# ArduinoMega.net
KiCad netlist of a schematic drawn in Altium Designer
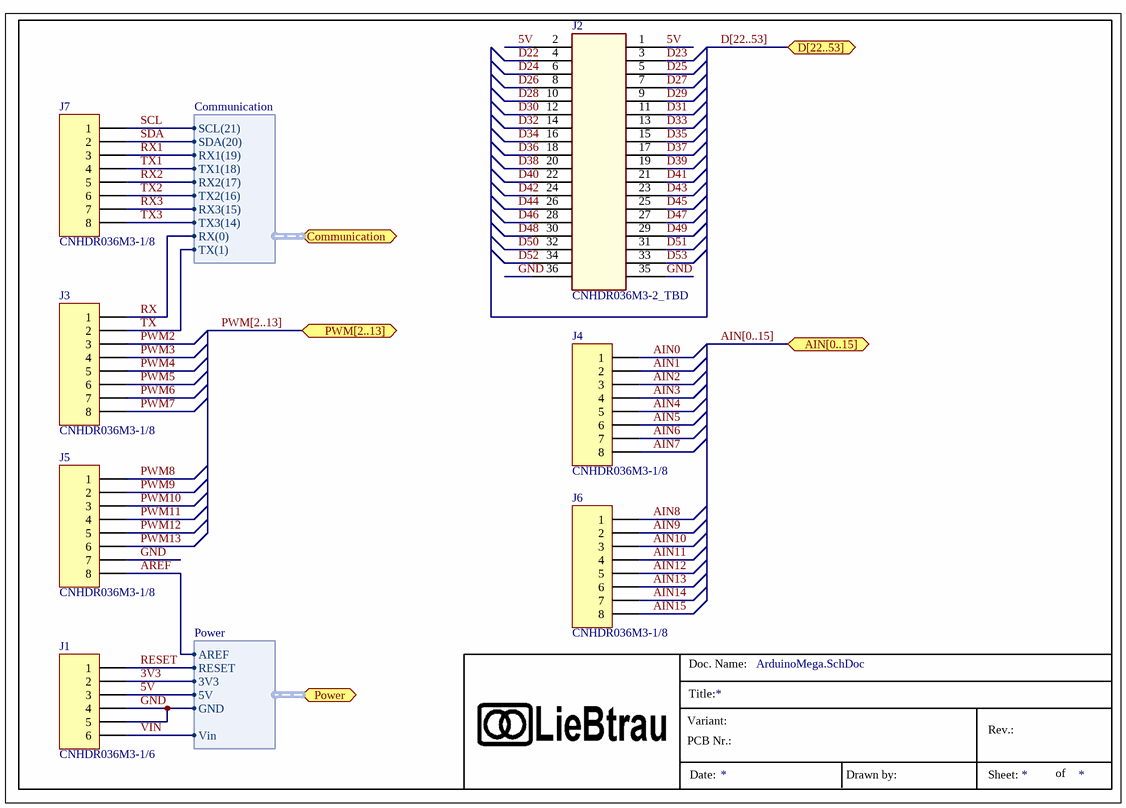
[diagram p0: ArduinoMega.SchDoc]

(export (version "E")
  (design (tool "Eeschema 10.0.6"))
  (components
    (comp (ref "J1")
      (value "CNHDR036M3-1/6")
      (footprint "J_HDR1X6")
      (libsource (lib "Testing") (part "J_6P"))
    )
    (comp (ref "J2")
      (value "CNHDR036M3-2_TBD")
      (footprint "J_HDR2X18")
      (libsource (lib "Testing") (part "J_2X18P"))
    )
    (comp (ref "J3")
      (value "CNHDR036M3-1/8")
      (footprint "J_HDR1X8")
      (libsource (lib "Testing") (part "J_8P"))
    )
    (comp (ref "J4")
      (value "CNHDR036M3-1/8")
      (footprint "J_HDR1X8")
      (libsource (lib "Testing") (part "J_8P"))
    )
    (comp (ref "J5")
      (value "CNHDR036M3-1/8")
      (footprint "J_HDR1X8")
      (libsource (lib "Testing") (part "J_8P"))
    )
    (comp (ref "J6")
      (value "CNHDR036M3-1/8")
      (footprint "J_HDR1X8")
      (libsource (lib "Testing") (part "J_8P"))
    )
    (comp (ref "J7")
      (value "CNHDR036M3-1/8")
      (footprint "J_HDR1X8")
      (libsource (lib "Testing") (part "J_8P"))
    )
  )
  (nets
    (net (code "3") (name "/3V3") (class "Default")
      (node (ref "J1") (pin "2") (pinfunction "2_2") (pintype "passive"))
    )
    (net (code "4") (name "/5V") (class "Default")
      (node (ref "J1") (pin "3") (pinfunction "3_3") (pintype "passive"))
      (node (ref "J2") (pin "1") (pinfunction "1_1") (pintype "passive"))
      (node (ref "J2") (pin "2") (pinfunction "2_2") (pintype "passive"))
    )
    (net (code "5") (name "/AIN0") (class "Default")
      (node (ref "J4") (pin "1") (pinfunction "1_1") (pintype "passive"))
    )
    (net (code "6") (name "/AIN1") (class "Default")
      (node (ref "J4") (pin "2") (pinfunction "2_2") (pintype "passive"))
    )
    (net (code "7") (name "/AIN2") (class "Default")
      (node (ref "J4") (pin "3") (pinfunction "3_3") (pintype "passive"))
    )
    (net (code "8") (name "/AIN3") (class "Default")
      (node (ref "J4") (pin "4") (pinfunction "4_4") (pintype "passive"))
    )
    (net (code "9") (name "/AIN4") (class "Default")
      (node (ref "J4") (pin "5") (pinfunction "5_5") (pintype "passive"))
    )
    (net (code "10") (name "/AIN5") (class "Default")
      (node (ref "J4") (pin "6") (pinfunction "6_6") (pintype "passive"))
    )
    (net (code "11") (name "/AIN6") (class "Default")
      (node (ref "J4") (pin "7") (pinfunction "7_7") (pintype "passive"))
    )
    (net (code "12") (name "/AIN7") (class "Default")
      (node (ref "J4") (pin "8") (pinfunction "8_8") (pintype "passive"))
    )
    (net (code "13") (name "/AIN8") (class "Default")
      (node (ref "J6") (pin "1") (pinfunction "1_1") (pintype "passive"))
    )
    (net (code "14") (name "/AIN9") (class "Default")
      (node (ref "J6") (pin "2") (pinfunction "2_2") (pintype "passive"))
    )
    (net (code "15") (name "/AIN10") (class "Default")
      (node (ref "J6") (pin "3") (pinfunction "3_3") (pintype "passive"))
    )
    (net (code "16") (name "/AIN11") (class "Default")
      (node (ref "J6") (pin "4") (pinfunction "4_4") (pintype "passive"))
    )
    (net (code "17") (name "/AIN12") (class "Default")
      (node (ref "J6") (pin "5") (pinfunction "5_5") (pintype "passive"))
    )
    (net (code "18") (name "/AIN13") (class "Default")
      (node (ref "J6") (pin "6") (pinfunction "6_6") (pintype "passive"))
    )
    (net (code "19") (name "/AIN14") (class "Default")
      (node (ref "J6") (pin "7") (pinfunction "7_7") (pintype "passive"))
    )
    (net (code "20") (name "/AIN15") (class "Default")
      (node (ref "J6") (pin "8") (pinfunction "8_8") (pintype "passive"))
    )
    (net (code "22") (name "/AREF") (class "Default")
      (node (ref "J5") (pin "8") (pinfunction "8_8") (pintype "passive"))
    )
    (net (code "23") (name "/D22") (class "Default")
      (node (ref "J2") (pin "4") (pinfunction "4_4") (pintype "passive"))
    )
    (net (code "24") (name "/D23") (class "Default")
      (node (ref "J2") (pin "3") (pinfunction "3_3") (pintype "passive"))
    )
    (net (code "25") (name "/D24") (class "Default")
      (node (ref "J2") (pin "6") (pinfunction "6_6") (pintype "passive"))
    )
    (net (code "26") (name "/D25") (class "Default")
      (node (ref "J2") (pin "5") (pinfunction "5_5") (pintype "passive"))
    )
    (net (code "27") (name "/D26") (class "Default")
      (node (ref "J2") (pin "8") (pinfunction "8_8") (pintype "passive"))
    )
    (net (code "28") (name "/D27") (class "Default")
      (node (ref "J2") (pin "7") (pinfunction "7_7") (pintype "passive"))
    )
    (net (code "29") (name "/D28") (class "Default")
      (node (ref "J2") (pin "10") (pinfunction "10_10") (pintype "passive"))
    )
    (net (code "30") (name "/D29") (class "Default")
      (node (ref "J2") (pin "9") (pinfunction "9_9") (pintype "passive"))
    )
    (net (code "31") (name "/D30") (class "Default")
      (node (ref "J2") (pin "12") (pinfunction "12_12") (pintype "passive"))
    )
    (net (code "32") (name "/D31") (class "Default")
      (node (ref "J2") (pin "11") (pinfunction "11_11") (pintype "passive"))
    )
    (net (code "33") (name "/D32") (class "Default")
      (node (ref "J2") (pin "14") (pinfunction "14_14") (pintype "passive"))
    )
    (net (code "34") (name "/D33") (class "Default")
      (node (ref "J2") (pin "13") (pinfunction "13_13") (pintype "passive"))
    )
    (net (code "35") (name "/D34") (class "Default")
      (node (ref "J2") (pin "16") (pinfunction "16_16") (pintype "passive"))
    )
    (net (code "36") (name "/D35") (class "Default")
      (node (ref "J2") (pin "15") (pinfunction "15_15") (pintype "passive"))
    )
    (net (code "37") (name "/D36") (class "Default")
      (node (ref "J2") (pin "18") (pinfunction "18_18") (pintype "passive"))
    )
    (net (code "38") (name "/D37") (class "Default")
      (node (ref "J2") (pin "17") (pinfunction "17_17") (pintype "passive"))
    )
    (net (code "39") (name "/D38") (class "Default")
      (node (ref "J2") (pin "20") (pinfunction "20_20") (pintype "passive"))
    )
    (net (code "40") (name "/D39") (class "Default")
      (node (ref "J2") (pin "19") (pinfunction "19_19") (pintype "passive"))
    )
    (net (code "41") (name "/D40") (class "Default")
      (node (ref "J2") (pin "22") (pinfunction "22_22") (pintype "passive"))
    )
    (net (code "42") (name "/D41") (class "Default")
      (node (ref "J2") (pin "21") (pinfunction "21_21") (pintype "passive"))
    )
    (net (code "43") (name "/D42") (class "Default")
      (node (ref "J2") (pin "24") (pinfunction "24_24") (pintype "passive"))
    )
    (net (code "44") (name "/D43") (class "Default")
      (node (ref "J2") (pin "23") (pinfunction "23_23") (pintype "passive"))
    )
    (net (code "45") (name "/D44") (class "Default")
      (node (ref "J2") (pin "26") (pinfunction "26_26") (pintype "passive"))
    )
    (net (code "46") (name "/D45") (class "Default")
      (node (ref "J2") (pin "25") (pinfunction "25_25") (pintype "passive"))
    )
    (net (code "47") (name "/D46") (class "Default")
      (node (ref "J2") (pin "28") (pinfunction "28_28") (pintype "passive"))
    )
    (net (code "48") (name "/D47") (class "Default")
      (node (ref "J2") (pin "27") (pinfunction "27_27") (pintype "passive"))
    )
    (net (code "49") (name "/D48") (class "Default")
      (node (ref "J2") (pin "30") (pinfunction "30_30") (pintype "passive"))
    )
    (net (code "50") (name "/D49") (class "Default")
      (node (ref "J2") (pin "29") (pinfunction "29_29") (pintype "passive"))
    )
    (net (code "51") (name "/D50") (class "Default")
      (node (ref "J2") (pin "32") (pinfunction "32_32") (pintype "passive"))
    )
    (net (code "52") (name "/D51") (class "Default")
      (node (ref "J2") (pin "31") (pinfunction "31_31") (pintype "passive"))
    )
    (net (code "53") (name "/D52") (class "Default")
      (node (ref "J2") (pin "34") (pinfunction "34_34") (pintype "passive"))
    )
    (net (code "54") (name "/D53") (class "Default")
      (node (ref "J2") (pin "33") (pinfunction "33_33") (pintype "passive"))
    )
    (net (code "56") (name "/GND") (class "Default")
      (node (ref "J1") (pin "4") (pinfunction "4_4") (pintype "passive"))
      (node (ref "J1") (pin "5") (pinfunction "5_5") (pintype "passive"))
      (node (ref "J2") (pin "35") (pinfunction "35_35") (pintype "passive"))
      (node (ref "J2") (pin "36") (pinfunction "36_36") (pintype "passive"))
      (node (ref "J5") (pin "7") (pinfunction "7_7") (pintype "passive"))
    )
    (net (code "57") (name "/PWM2") (class "Default")
      (node (ref "J3") (pin "3") (pinfunction "3_3") (pintype "passive"))
    )
    (net (code "58") (name "/PWM3") (class "Default")
      (node (ref "J3") (pin "4") (pinfunction "4_4") (pintype "passive"))
    )
    (net (code "59") (name "/PWM4") (class "Default")
      (node (ref "J3") (pin "5") (pinfunction "5_5") (pintype "passive"))
    )
    (net (code "60") (name "/PWM5") (class "Default")
      (node (ref "J3") (pin "6") (pinfunction "6_6") (pintype "passive"))
    )
    (net (code "61") (name "/PWM6") (class "Default")
      (node (ref "J3") (pin "7") (pinfunction "7_7") (pintype "passive"))
    )
    (net (code "62") (name "/PWM7") (class "Default")
      (node (ref "J3") (pin "8") (pinfunction "8_8") (pintype "passive"))
    )
    (net (code "63") (name "/PWM8") (class "Default")
      (node (ref "J5") (pin "1") (pinfunction "1_1") (pintype "passive"))
    )
    (net (code "64") (name "/PWM9") (class "Default")
      (node (ref "J5") (pin "2") (pinfunction "2_2") (pintype "passive"))
    )
    (net (code "65") (name "/PWM10") (class "Default")
      (node (ref "J5") (pin "3") (pinfunction "3_3") (pintype "passive"))
    )
    (net (code "66") (name "/PWM11") (class "Default")
      (node (ref "J5") (pin "4") (pinfunction "4_4") (pintype "passive"))
    )
    (net (code "67") (name "/PWM12") (class "Default")
      (node (ref "J5") (pin "5") (pinfunction "5_5") (pintype "passive"))
    )
    (net (code "68") (name "/PWM13") (class "Default")
      (node (ref "J5") (pin "6") (pinfunction "6_6") (pintype "passive"))
    )
    (net (code "70") (name "/RESET") (class "Default")
      (node (ref "J1") (pin "1") (pinfunction "1_1") (pintype "passive"))
    )
    (net (code "71") (name "/RX") (class "Default")
      (node (ref "J3") (pin "1") (pinfunction "1_1") (pintype "passive"))
    )
    (net (code "72") (name "/RX1") (class "Default")
      (node (ref "J7") (pin "3") (pinfunction "3_3") (pintype "passive"))
    )
    (net (code "73") (name "/RX2") (class "Default")
      (node (ref "J7") (pin "5") (pinfunction "5_5") (pintype "passive"))
    )
    (net (code "74") (name "/RX3") (class "Default")
      (node (ref "J7") (pin "7") (pinfunction "7_7") (pintype "passive"))
    )
    (net (code "75") (name "/SCL") (class "Default")
      (node (ref "J7") (pin "1") (pinfunction "1_1") (pintype "passive"))
    )
    (net (code "76") (name "/SDA") (class "Default")
      (node (ref "J7") (pin "2") (pinfunction "2_2") (pintype "passive"))
    )
    (net (code "77") (name "/TX") (class "Default")
      (node (ref "J3") (pin "2") (pinfunction "2_2") (pintype "passive"))
    )
    (net (code "78") (name "/TX1") (class "Default")
      (node (ref "J7") (pin "4") (pinfunction "4_4") (pintype "passive"))
    )
    (net (code "79") (name "/TX2") (class "Default")
      (node (ref "J7") (pin "6") (pinfunction "6_6") (pintype "passive"))
    )
    (net (code "80") (name "/TX3") (class "Default")
      (node (ref "J7") (pin "8") (pinfunction "8_8") (pintype "passive"))
    )
    (net (code "81") (name "/VIN") (class "Default")
      (node (ref "J1") (pin "6") (pinfunction "6_6") (pintype "passive"))
    )
  )
)
